# me433-hw4.net
KiCad netlist of a schematic drawn in EAGLE
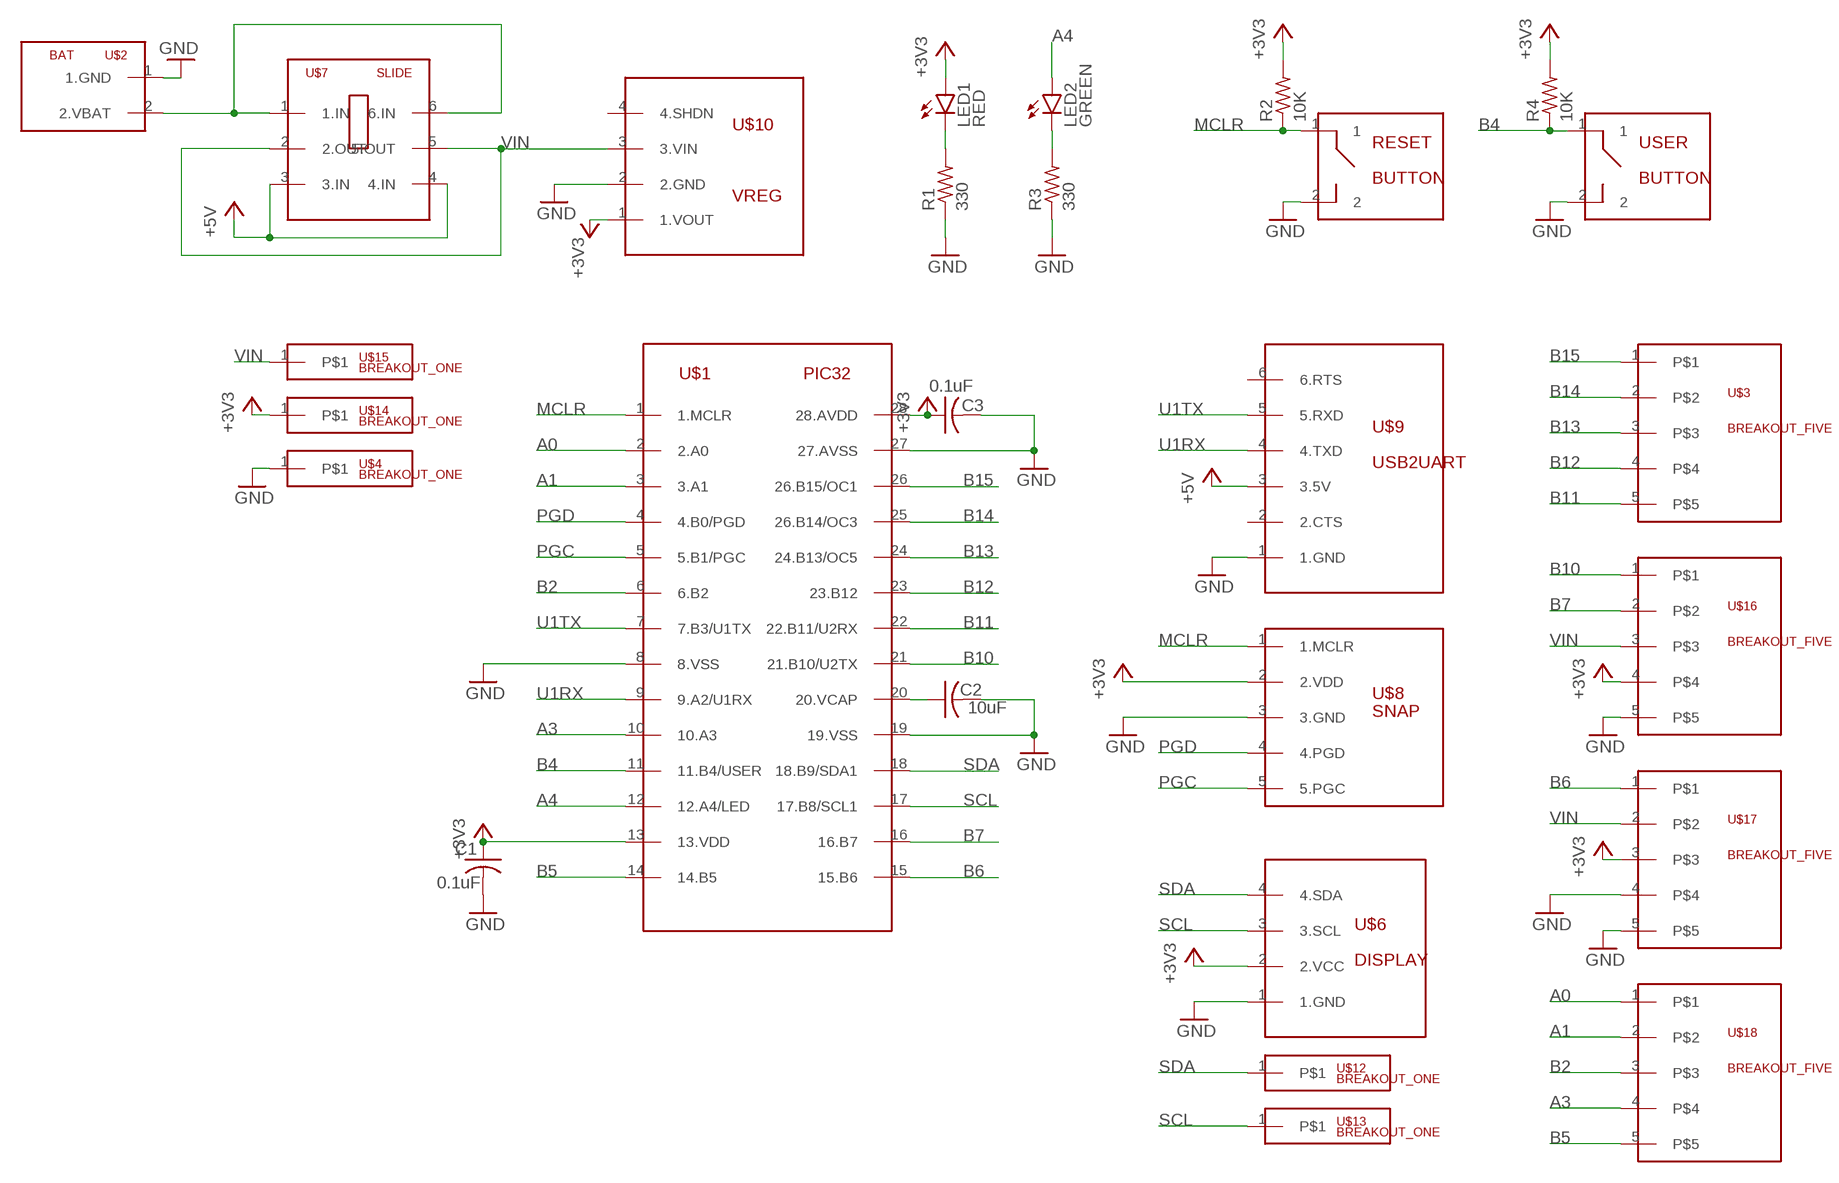
[diagram p0: schematic, sheet 1]

(export (version "E")
  (design (tool "Eeschema 10.0.6"))
  (components
    (comp (ref "C1")
      (value "0.1uF")
      (footprint "eagle-import:C025-024X044")
      (libsource (lib "eagle-import") (part "C-US025-024X044"))
    )
    (comp (ref "C2")
      (value "10uF")
      (footprint "eagle-import:C025-024X044")
      (libsource (lib "eagle-import") (part "C-US025-024X044"))
    )
    (comp (ref "C3")
      (value "0.1uF")
      (footprint "eagle-import:C025-024X044")
      (libsource (lib "eagle-import") (part "C-US025-024X044"))
    )
    (comp (ref "LED1")
      (value "RED")
      (footprint "eagle-import:LED3MM")
      (libsource (lib "eagle-import") (part "LED3MM"))
    )
    (comp (ref "LED2")
      (value "GREEN")
      (footprint "eagle-import:LED3MM")
      (libsource (lib "eagle-import") (part "LED3MM"))
    )
    (comp (ref "R1")
      (value "330")
      (footprint "eagle-import:0207_7")
      (libsource (lib "eagle-import") (part "R-US_0207/7"))
    )
    (comp (ref "R2")
      (value "10K")
      (footprint "eagle-import:0207_7")
      (libsource (lib "eagle-import") (part "R-US_0207/7"))
    )
    (comp (ref "R3")
      (value "330")
      (footprint "eagle-import:0207_7")
      (libsource (lib "eagle-import") (part "R-US_0207/7"))
    )
    (comp (ref "R4")
      (value "10K")
      (footprint "eagle-import:0207_7")
      (libsource (lib "eagle-import") (part "R-US_0207/7"))
    )
    (comp (ref "RESET")
      (value "BUTTON")
      (footprint "eagle-import:BUTTON")
      (libsource (lib "eagle-import") (part "BUTTON"))
    )
    (comp (ref "U$1")
      (value "PIC32")
      (footprint "eagle-import:DIL28-3")
      (libsource (lib "eagle-import") (part "PIC32"))
    )
    (comp (ref "U$2")
      (value "BAT")
      (footprint "eagle-import:BAT")
      (libsource (lib "eagle-import") (part "BAT"))
    )
    (comp (ref "U$3")
      (value "BREAKOUT_FIVE")
      (footprint "eagle-import:BREAKOUT_FIVE")
      (libsource (lib "eagle-import") (part "BREAKOUT_FIVE"))
    )
    (comp (ref "U$4")
      (value "BREAKOUT_ONE")
      (footprint "eagle-import:BREAKOUT_ONE")
      (libsource (lib "eagle-import") (part "BREAKOUT_ONE"))
    )
    (comp (ref "U$6")
      (value "DISPLAY")
      (footprint "eagle-import:DISPLAY")
      (libsource (lib "eagle-import") (part "DISPLAY"))
    )
    (comp (ref "U$7")
      (value "SLIDE")
      (footprint "eagle-import:SLIDE")
      (libsource (lib "eagle-import") (part "SLIDE"))
    )
    (comp (ref "U$8")
      (value "SNAP")
      (footprint "eagle-import:SNAP")
      (libsource (lib "eagle-import") (part "SNAP"))
    )
    (comp (ref "U$9")
      (value "USB2UART")
      (footprint "eagle-import:USB2UART")
      (libsource (lib "eagle-import") (part "USB2UART"))
    )
    (comp (ref "U$10")
      (value "VREG")
      (footprint "eagle-import:VREG")
      (libsource (lib "eagle-import") (part "VREG"))
    )
    (comp (ref "U$12")
      (value "BREAKOUT_ONE")
      (footprint "eagle-import:BREAKOUT_ONE")
      (libsource (lib "eagle-import") (part "BREAKOUT_ONE"))
    )
    (comp (ref "U$13")
      (value "BREAKOUT_ONE")
      (footprint "eagle-import:BREAKOUT_ONE")
      (libsource (lib "eagle-import") (part "BREAKOUT_ONE"))
    )
    (comp (ref "U$14")
      (value "BREAKOUT_ONE")
      (footprint "eagle-import:BREAKOUT_ONE")
      (libsource (lib "eagle-import") (part "BREAKOUT_ONE"))
    )
    (comp (ref "U$15")
      (value "BREAKOUT_ONE")
      (footprint "eagle-import:BREAKOUT_ONE")
      (libsource (lib "eagle-import") (part "BREAKOUT_ONE"))
    )
    (comp (ref "U$16")
      (value "BREAKOUT_FIVE")
      (footprint "eagle-import:BREAKOUT_FIVE")
      (libsource (lib "eagle-import") (part "BREAKOUT_FIVE"))
    )
    (comp (ref "U$17")
      (value "BREAKOUT_FIVE")
      (footprint "eagle-import:BREAKOUT_FIVE")
      (libsource (lib "eagle-import") (part "BREAKOUT_FIVE"))
    )
    (comp (ref "U$18")
      (value "BREAKOUT_FIVE")
      (footprint "eagle-import:BREAKOUT_FIVE")
      (libsource (lib "eagle-import") (part "BREAKOUT_FIVE"))
    )
    (comp (ref "USER")
      (value "BUTTON")
      (footprint "eagle-import:BUTTON")
      (libsource (lib "eagle-import") (part "BUTTON"))
    )
  )
  (nets
    (net (code "1") (name "+3V3") (class "Default")
      (node (ref "C1") (pin "1") (pinfunction "1_1") (pintype "passive"))
      (node (ref "C3") (pin "1") (pinfunction "1_1") (pintype "passive"))
      (node (ref "LED1") (pin "A") (pinfunction "A_A") (pintype "passive"))
      (node (ref "R2") (pin "2") (pinfunction "2_2") (pintype "passive"))
      (node (ref "R4") (pin "2") (pinfunction "2_2") (pintype "passive"))
      (node (ref "U$1") (pin "13") (pinfunction "13.VDD_13") (pintype "bidirectional"))
      (node (ref "U$1") (pin "28") (pinfunction "28.AVDD_28") (pintype "bidirectional"))
      (node (ref "U$10") (pin "1") (pinfunction "1.VOUT_1") (pintype "bidirectional"))
      (node (ref "U$14") (pin "1") (pinfunction "P$1_1") (pintype "bidirectional"))
      (node (ref "U$16") (pin "4") (pinfunction "P$4_4") (pintype "bidirectional"))
      (node (ref "U$17") (pin "3") (pinfunction "P$3_3") (pintype "bidirectional"))
      (node (ref "U$6") (pin "2") (pinfunction "2.VCC_2") (pintype "bidirectional"))
      (node (ref "U$8") (pin "2") (pinfunction "2.VDD_2") (pintype "bidirectional"))
    )
    (net (code "2") (name "+5V") (class "Default")
      (node (ref "U$7") (pin "3") (pinfunction "3.IN_3") (pintype "bidirectional"))
      (node (ref "U$7") (pin "4") (pinfunction "4.IN_4") (pintype "bidirectional"))
      (node (ref "U$9") (pin "3") (pinfunction "3.5V_3") (pintype "bidirectional"))
    )
    (net (code "3") (name "/A0") (class "Default")
      (node (ref "U$1") (pin "2") (pinfunction "2.A0_2") (pintype "bidirectional"))
      (node (ref "U$18") (pin "1") (pinfunction "P$1_1") (pintype "bidirectional"))
    )
    (net (code "4") (name "/A1") (class "Default")
      (node (ref "U$1") (pin "3") (pinfunction "3.A1_3") (pintype "bidirectional"))
      (node (ref "U$18") (pin "2") (pinfunction "P$2_2") (pintype "bidirectional"))
    )
    (net (code "5") (name "/A3") (class "Default")
      (node (ref "U$1") (pin "10") (pinfunction "10.A3_10") (pintype "bidirectional"))
      (node (ref "U$18") (pin "4") (pinfunction "P$4_4") (pintype "bidirectional"))
    )
    (net (code "6") (name "/A4") (class "Default")
      (node (ref "LED2") (pin "A") (pinfunction "A_A") (pintype "passive"))
      (node (ref "U$1") (pin "12") (pinfunction "12.A4/LED_12") (pintype "bidirectional"))
    )
    (net (code "7") (name "/B2") (class "Default")
      (node (ref "U$1") (pin "6") (pinfunction "6.B2_6") (pintype "bidirectional"))
      (node (ref "U$18") (pin "3") (pinfunction "P$3_3") (pintype "bidirectional"))
    )
    (net (code "8") (name "/B4") (class "Default")
      (node (ref "R4") (pin "1") (pinfunction "1_1") (pintype "passive"))
      (node (ref "U$1") (pin "11") (pinfunction "11.B4/USER_11") (pintype "bidirectional"))
      (node (ref "USER") (pin "1") (pinfunction "1_1") (pintype "bidirectional"))
    )
    (net (code "9") (name "/B5") (class "Default")
      (node (ref "U$1") (pin "14") (pinfunction "14.B5_14") (pintype "bidirectional"))
      (node (ref "U$18") (pin "5") (pinfunction "P$5_5") (pintype "bidirectional"))
    )
    (net (code "10") (name "/B6") (class "Default")
      (node (ref "U$1") (pin "15") (pinfunction "15.B6_15") (pintype "bidirectional"))
      (node (ref "U$17") (pin "1") (pinfunction "P$1_1") (pintype "bidirectional"))
    )
    (net (code "11") (name "/B7") (class "Default")
      (node (ref "U$1") (pin "16") (pinfunction "16.B7_16") (pintype "bidirectional"))
      (node (ref "U$16") (pin "2") (pinfunction "P$2_2") (pintype "bidirectional"))
    )
    (net (code "12") (name "/B10") (class "Default")
      (node (ref "U$1") (pin "21") (pinfunction "21.B10/U2TX_21") (pintype "bidirectional"))
      (node (ref "U$16") (pin "1") (pinfunction "P$1_1") (pintype "bidirectional"))
    )
    (net (code "13") (name "/B11") (class "Default")
      (node (ref "U$1") (pin "22") (pinfunction "22.B11/U2RX_22") (pintype "bidirectional"))
      (node (ref "U$3") (pin "5") (pinfunction "P$5_5") (pintype "bidirectional"))
    )
    (net (code "14") (name "/B12") (class "Default")
      (node (ref "U$1") (pin "23") (pinfunction "23.B12_23") (pintype "bidirectional"))
      (node (ref "U$3") (pin "4") (pinfunction "P$4_4") (pintype "bidirectional"))
    )
    (net (code "15") (name "/B13") (class "Default")
      (node (ref "U$1") (pin "24") (pinfunction "24.B13/OC5_24") (pintype "bidirectional"))
      (node (ref "U$3") (pin "3") (pinfunction "P$3_3") (pintype "bidirectional"))
    )
    (net (code "16") (name "/B14") (class "Default")
      (node (ref "U$1") (pin "25") (pinfunction "26.B14/OC3_25") (pintype "bidirectional"))
      (node (ref "U$3") (pin "2") (pinfunction "P$2_2") (pintype "bidirectional"))
    )
    (net (code "17") (name "/B15") (class "Default")
      (node (ref "U$1") (pin "26") (pinfunction "26.B15/OC1_26") (pintype "bidirectional"))
      (node (ref "U$3") (pin "1") (pinfunction "P$1_1") (pintype "bidirectional"))
    )
    (net (code "18") (name "/MCLR") (class "Default")
      (node (ref "R2") (pin "1") (pinfunction "1_1") (pintype "passive"))
      (node (ref "RESET") (pin "1") (pinfunction "1_1") (pintype "bidirectional"))
      (node (ref "U$1") (pin "1") (pinfunction "1.MCLR_1") (pintype "bidirectional"))
      (node (ref "U$8") (pin "1") (pinfunction "1.MCLR_1") (pintype "bidirectional"))
    )
    (net (code "19") (name "/PGC") (class "Default")
      (node (ref "U$1") (pin "5") (pinfunction "5.B1/PGC_5") (pintype "bidirectional"))
      (node (ref "U$8") (pin "5") (pinfunction "5.PGC_5") (pintype "bidirectional"))
    )
    (net (code "20") (name "/PGD") (class "Default")
      (node (ref "U$1") (pin "4") (pinfunction "4.B0/PGD_4") (pintype "bidirectional"))
      (node (ref "U$8") (pin "4") (pinfunction "4.PGD_4") (pintype "bidirectional"))
    )
    (net (code "21") (name "/SCL") (class "Default")
      (node (ref "U$1") (pin "17") (pinfunction "17.B8/SCL1_17") (pintype "bidirectional"))
      (node (ref "U$13") (pin "1") (pinfunction "P$1_1") (pintype "bidirectional"))
      (node (ref "U$6") (pin "3") (pinfunction "3.SCL_3") (pintype "bidirectional"))
    )
    (net (code "22") (name "/SDA") (class "Default")
      (node (ref "U$1") (pin "18") (pinfunction "18.B9/SDA1_18") (pintype "bidirectional"))
      (node (ref "U$12") (pin "1") (pinfunction "P$1_1") (pintype "bidirectional"))
      (node (ref "U$6") (pin "4") (pinfunction "4.SDA_4") (pintype "bidirectional"))
    )
    (net (code "23") (name "/U1RX") (class "Default")
      (node (ref "U$1") (pin "9") (pinfunction "9.A2/U1RX_9") (pintype "bidirectional"))
      (node (ref "U$9") (pin "4") (pinfunction "4.TXD_4") (pintype "bidirectional"))
    )
    (net (code "24") (name "/U1TX") (class "Default")
      (node (ref "U$1") (pin "7") (pinfunction "7.B3/U1TX_7") (pintype "bidirectional"))
      (node (ref "U$9") (pin "5") (pinfunction "5.RXD_5") (pintype "bidirectional"))
    )
    (net (code "25") (name "/VIN") (class "Default")
      (node (ref "U$10") (pin "3") (pinfunction "3.VIN_3") (pintype "bidirectional"))
      (node (ref "U$15") (pin "1") (pinfunction "P$1_1") (pintype "bidirectional"))
      (node (ref "U$16") (pin "3") (pinfunction "P$3_3") (pintype "bidirectional"))
      (node (ref "U$17") (pin "2") (pinfunction "P$2_2") (pintype "bidirectional"))
      (node (ref "U$7") (pin "2") (pinfunction "2.OUT_2") (pintype "bidirectional"))
      (node (ref "U$7") (pin "5") (pinfunction "5.OUT_5") (pintype "bidirectional"))
    )
    (net (code "26") (name "GND") (class "Default")
      (node (ref "C1") (pin "2") (pinfunction "2_2") (pintype "passive"))
      (node (ref "C2") (pin "2") (pinfunction "2_2") (pintype "passive"))
      (node (ref "C3") (pin "2") (pinfunction "2_2") (pintype "passive"))
      (node (ref "R1") (pin "1") (pinfunction "1_1") (pintype "passive"))
      (node (ref "R3") (pin "1") (pinfunction "1_1") (pintype "passive"))
      (node (ref "RESET") (pin "2") (pinfunction "2_2") (pintype "bidirectional"))
      (node (ref "U$1") (pin "19") (pinfunction "19.VSS_19") (pintype "bidirectional"))
      (node (ref "U$1") (pin "27") (pinfunction "27.AVSS_27") (pintype "bidirectional"))
      (node (ref "U$1") (pin "8") (pinfunction "8.VSS_8") (pintype "bidirectional"))
      (node (ref "U$10") (pin "2") (pinfunction "2.GND_2") (pintype "bidirectional"))
      (node (ref "U$16") (pin "5") (pinfunction "P$5_5") (pintype "bidirectional"))
      (node (ref "U$17") (pin "4") (pinfunction "P$4_4") (pintype "bidirectional"))
      (node (ref "U$17") (pin "5") (pinfunction "P$5_5") (pintype "bidirectional"))
      (node (ref "U$2") (pin "1") (pinfunction "1.GND_1") (pintype "bidirectional"))
      (node (ref "U$4") (pin "1") (pinfunction "P$1_1") (pintype "bidirectional"))
      (node (ref "U$6") (pin "1") (pinfunction "1.GND_1") (pintype "bidirectional"))
      (node (ref "U$8") (pin "3") (pinfunction "3.GND_3") (pintype "bidirectional"))
      (node (ref "U$9") (pin "1") (pinfunction "1.GND_1") (pintype "bidirectional"))
      (node (ref "USER") (pin "2") (pinfunction "2_2") (pintype "bidirectional"))
    )
    (net (code "27") (name "Net-(LED1-C)") (class "Default")
      (node (ref "LED1") (pin "K") (pinfunction "C_K") (pintype "passive"))
      (node (ref "R1") (pin "2") (pinfunction "2_2") (pintype "passive"))
    )
    (net (code "28") (name "Net-(LED2-C)") (class "Default")
      (node (ref "LED2") (pin "K") (pinfunction "C_K") (pintype "passive"))
      (node (ref "R3") (pin "2") (pinfunction "2_2") (pintype "passive"))
    )
    (net (code "29") (name "Net-(U$1-20.VCAP)") (class "Default")
      (node (ref "C2") (pin "1") (pinfunction "1_1") (pintype "passive"))
      (node (ref "U$1") (pin "20") (pinfunction "20.VCAP_20") (pintype "bidirectional"))
    )
    (net (code "30") (name "Net-(U$2-2.VBAT)") (class "Default")
      (node (ref "U$2") (pin "2") (pinfunction "2.VBAT_2") (pintype "bidirectional"))
      (node (ref "U$7") (pin "1") (pinfunction "1.IN_1") (pintype "bidirectional"))
      (node (ref "U$7") (pin "6") (pinfunction "6.IN_6") (pintype "bidirectional"))
    )
    (net (code "31") (name "unconnected-(U$9-2.CTS-Pad2)") (class "Default")
      (node (ref "U$9") (pin "2") (pinfunction "2.CTS_2") (pintype "bidirectional"))
    )
    (net (code "32") (name "unconnected-(U$9-6.RTS-Pad6)") (class "Default")
      (node (ref "U$9") (pin "6") (pinfunction "6.RTS_6") (pintype "bidirectional"))
    )
    (net (code "33") (name "unconnected-(U$10-4.SHDN-Pad4)") (class "Default")
      (node (ref "U$10") (pin "4") (pinfunction "4.SHDN_4") (pintype "bidirectional"))
    )
  )
)
